# pidshield-mk-3_2.net
KiCad netlist of a schematic drawn in EAGLE
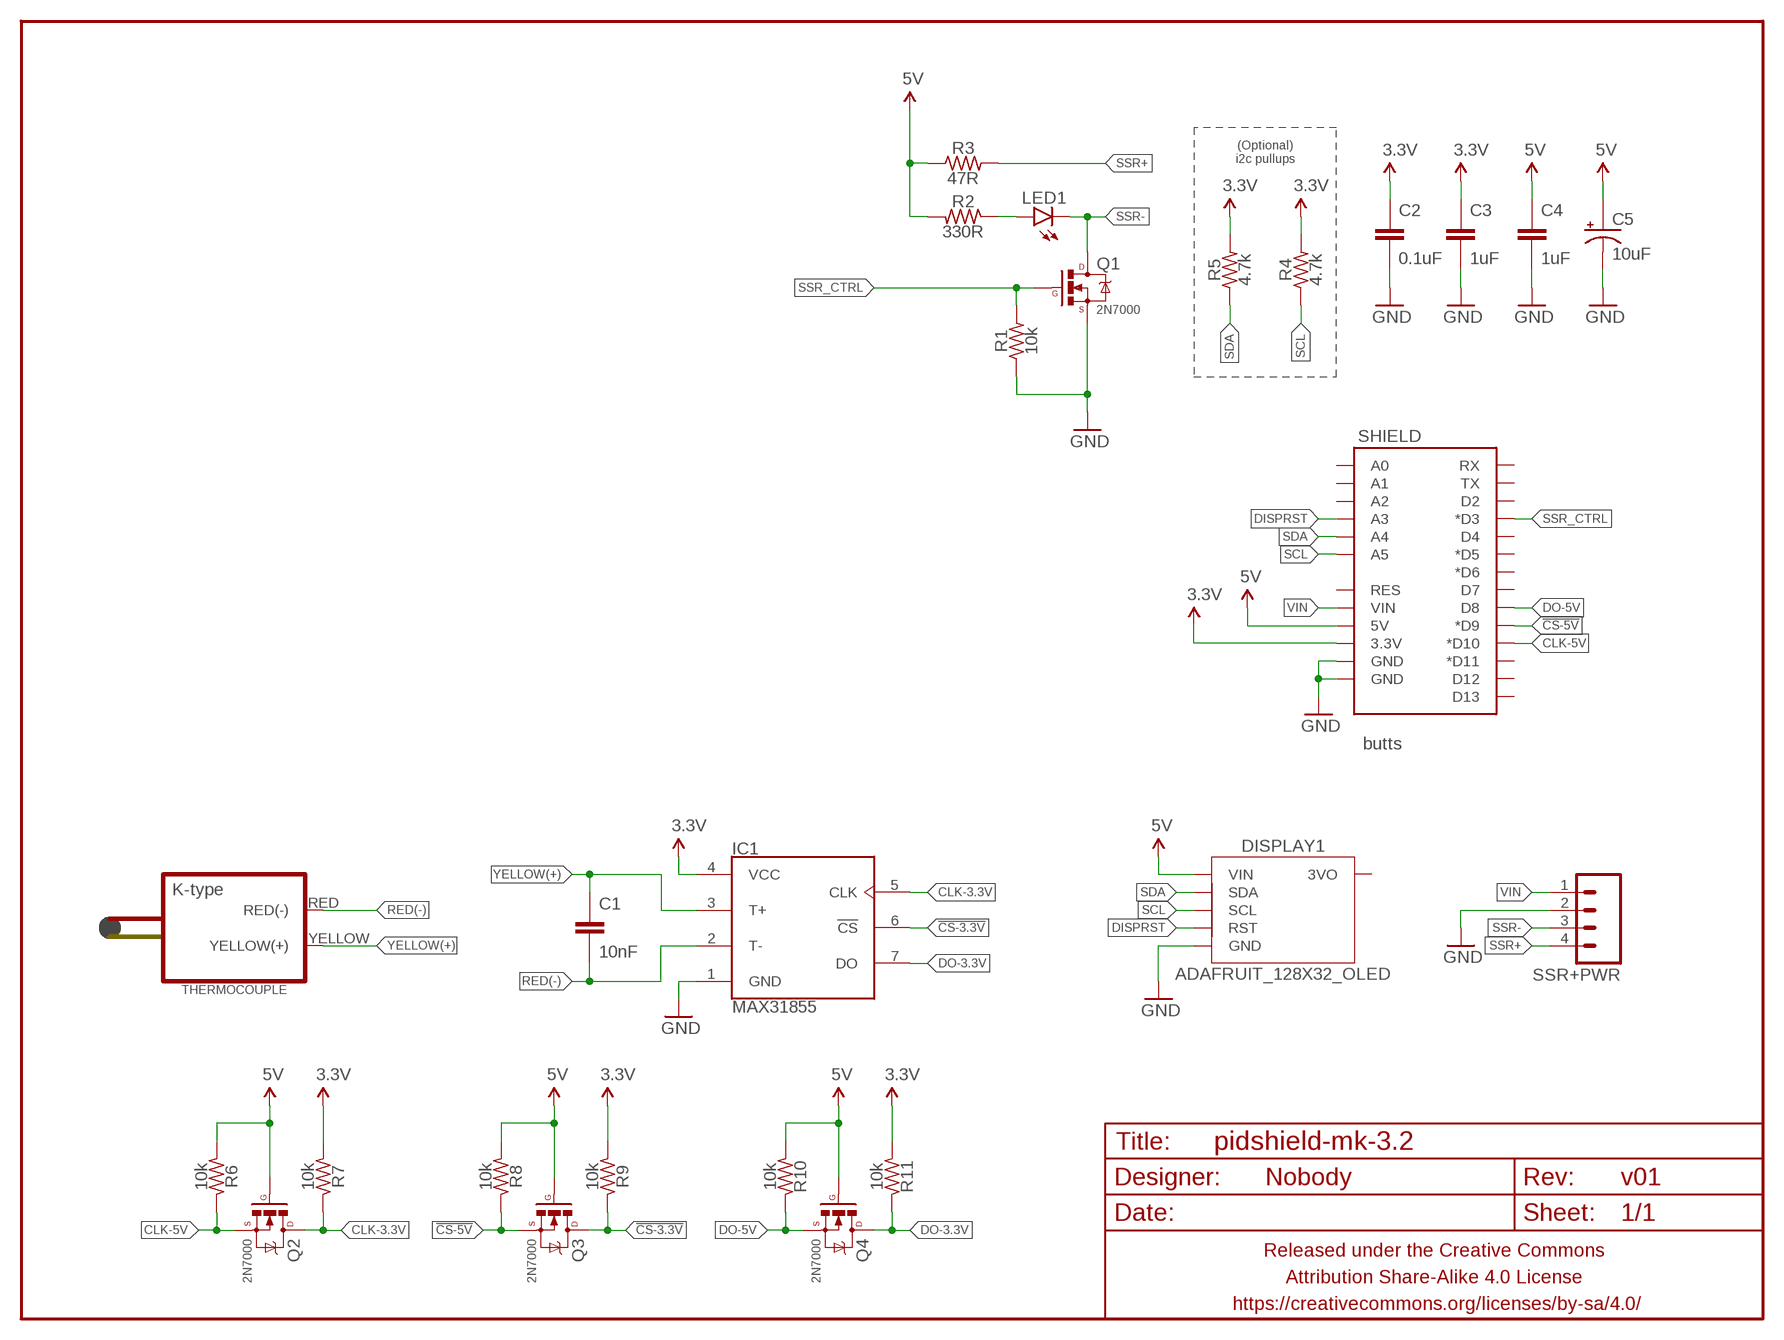
[diagram p0: schematic, sheet 1]

(export (version "E")
  (design (tool "Eeschema 10.0.6"))
  (components
    (comp (ref "C1")
      (value "10nF")
      (footprint "eagle-import:C0805")
      (libsource (lib "eagle-import") (part "CAPACITOR-CERAMICC0805"))
    )
    (comp (ref "C2")
      (value "0.1uF")
      (footprint "eagle-import:C025-024X044")
      (libsource (lib "eagle-import") (part "CAPACITOR-CERAMIC025-024X044"))
    )
    (comp (ref "C3")
      (value "1uF")
      (footprint "eagle-import:C025-024X044")
      (libsource (lib "eagle-import") (part "CAPACITOR-CERAMIC025-024X044"))
    )
    (comp (ref "C4")
      (value "1uF")
      (footprint "eagle-import:C025-024X044")
      (libsource (lib "eagle-import") (part "CAPACITOR-CERAMIC025-024X044"))
    )
    (comp (ref "C5")
      (value "10uF")
      (footprint "eagle-import:E2,5-6")
      (libsource (lib "eagle-import") (part "CAPACITOR-POLARIZEDE2.5-6"))
    )
    (comp (ref "DISPLAY1")
      (value "ADAFRUIT_128X32_OLED")
      (footprint "eagle-import:ADAFRUIT_128X32_OLED_I2C_CLOSER_NOTITLE")
      (libsource (lib "eagle-import") (part "ADAFRUIT_128X32_OLED_I2CNOTITLE"))
    )
    (comp (ref "FRAME1")
      (value "FRAME-LETTERNO_PACKAGE")
      (footprint "eagle-import:DUMMY")
      (fields (field (name "DESIGNER") "Nobody"))
      (libsource (lib "eagle-import") (part "FRAME-LETTERNO_PACKAGE"))
    )
    (comp (ref "IC1")
      (value "MAX31855")
      (footprint "eagle-import:SOIC127P600X175-8N")
      (libsource (lib "eagle-import") (part "MAX31855SOIC"))
    )
    (comp (ref "LED1")
      (value "LED3MM-LESS")
      (footprint "eagle-import:LED3MM-LESSSILK")
      (libsource (lib "eagle-import") (part "LED3MM-LESS"))
    )
    (comp (ref "Q1")
      (value "2N7000")
      (footprint "eagle-import:TO-92-AMMO")
      (libsource (lib "eagle-import") (part "MOSFET-NCHANNEL2N7000-AMMO"))
    )
    (comp (ref "Q2")
      (value "2N7000")
      (footprint "eagle-import:TO-92-AMMO")
      (libsource (lib "eagle-import") (part "MOSFET-NCHANNEL2N7000-AMMO"))
    )
    (comp (ref "Q3")
      (value "2N7000")
      (footprint "eagle-import:TO-92-AMMO")
      (libsource (lib "eagle-import") (part "MOSFET-NCHANNEL2N7000-AMMO"))
    )
    (comp (ref "Q4")
      (value "2N7000")
      (footprint "eagle-import:TO-92-AMMO")
      (libsource (lib "eagle-import") (part "MOSFET-NCHANNEL2N7000-AMMO"))
    )
    (comp (ref "R1")
      (value "10k")
      (footprint "eagle-import:RESISTOR-AXIAL-PTH-7.62MM")
      (libsource (lib "eagle-import") (part "RESISTORPTH-AXIAL-7.62MM"))
    )
    (comp (ref "R2")
      (value "330R")
      (footprint "eagle-import:RESISTOR-AXIAL-PTH-7.62MM")
      (libsource (lib "eagle-import") (part "RESISTORPTH-AXIAL-7.62MM"))
    )
    (comp (ref "R3")
      (value "47R")
      (footprint "eagle-import:RESISTOR-AXIAL-PTH-7.62MM")
      (libsource (lib "eagle-import") (part "RESISTORPTH-AXIAL-7.62MM"))
    )
    (comp (ref "R4")
      (value "4.7k")
      (footprint "eagle-import:RESISTOR-AXIAL-PTH-7.62MM")
      (libsource (lib "eagle-import") (part "RESISTORPTH-AXIAL-7.62MM"))
    )
    (comp (ref "R5")
      (value "4.7k")
      (footprint "eagle-import:RESISTOR-AXIAL-PTH-7.62MM")
      (libsource (lib "eagle-import") (part "RESISTORPTH-AXIAL-7.62MM"))
    )
    (comp (ref "R6")
      (value "10k")
      (footprint "eagle-import:RESISTOR-AXIAL-PTH-7.62MM")
      (libsource (lib "eagle-import") (part "RESISTORPTH-AXIAL-7.62MM"))
    )
    (comp (ref "R7")
      (value "10k")
      (footprint "eagle-import:RESISTOR-AXIAL-PTH-7.62MM")
      (libsource (lib "eagle-import") (part "RESISTORPTH-AXIAL-7.62MM"))
    )
    (comp (ref "R8")
      (value "10k")
      (footprint "eagle-import:RESISTOR-AXIAL-PTH-7.62MM")
      (libsource (lib "eagle-import") (part "RESISTORPTH-AXIAL-7.62MM"))
    )
    (comp (ref "R9")
      (value "10k")
      (footprint "eagle-import:RESISTOR-AXIAL-PTH-7.62MM")
      (libsource (lib "eagle-import") (part "RESISTORPTH-AXIAL-7.62MM"))
    )
    (comp (ref "R10")
      (value "10k")
      (footprint "eagle-import:RESISTOR-AXIAL-PTH-7.62MM")
      (libsource (lib "eagle-import") (part "RESISTORPTH-AXIAL-7.62MM"))
    )
    (comp (ref "R11")
      (value "10k")
      (footprint "eagle-import:RESISTOR-AXIAL-PTH-7.62MM")
      (libsource (lib "eagle-import") (part "RESISTORPTH-AXIAL-7.62MM"))
    )
    (comp (ref "SHIELD")
      (value "butts")
      (footprint "eagle-import:ARDUINO_SHIELD_SMALLER_NEKKID")
      (libsource (lib "eagle-import") (part "ARDUINO_SHIELD_SMALLERNEKKID"))
    )
    (comp (ref "SSR+PWR")
      (value "M04JST_XH_RA")
      (footprint "eagle-import:JST-4-XH-RA-PTH")
      (libsource (lib "eagle-import") (part "M04JST_XH_RA"))
    )
    (comp (ref "THERMOCOUPLE")
      (value "THERMOCOUPLE-CONNECTORMINI-PCB")
      (footprint "eagle-import:PCC-SMP")
      (libsource (lib "eagle-import") (part "THERMOCOUPLE-CONNECTORMINI-PCB"))
    )
  )
  (nets
    (net (code "1") (name "/~{CS-3.3V}") (class "Default")
      (node (ref "IC1") (pin "6") (pinfunction "~{CS}_6") (pintype "input"))
      (node (ref "Q3") (pin "3") (pinfunction "D_3") (pintype "passive"))
      (node (ref "R9") (pin "P$1") (pinfunction "1_P$1") (pintype "passive"))
    )
    (net (code "2") (name "/~{CS-5V}") (class "Default")
      (node (ref "Q3") (pin "1") (pinfunction "S_1") (pintype "passive"))
      (node (ref "R8") (pin "P$1") (pinfunction "1_P$1") (pintype "passive"))
      (node (ref "SHIELD") (pin "D9") (pinfunction "*D9_D9") (pintype "bidirectional"))
    )
    (net (code "3") (name "3.3V") (class "Default")
      (node (ref "C2") (pin "1") (pinfunction "1_1") (pintype "passive"))
      (node (ref "C3") (pin "1") (pinfunction "1_1") (pintype "passive"))
      (node (ref "IC1") (pin "4") (pinfunction "VCC_4") (pintype "power_in"))
      (node (ref "R11") (pin "P$2") (pinfunction "2_P$2") (pintype "passive"))
      (node (ref "R4") (pin "P$2") (pinfunction "2_P$2") (pintype "passive"))
      (node (ref "R5") (pin "P$2") (pinfunction "2_P$2") (pintype "passive"))
      (node (ref "R7") (pin "P$2") (pinfunction "2_P$2") (pintype "passive"))
      (node (ref "R9") (pin "P$2") (pinfunction "2_P$2") (pintype "passive"))
      (node (ref "SHIELD") (pin "3.3V") (pinfunction "3.3V_3.3V") (pintype "bidirectional"))
    )
    (net (code "4") (name "5V") (class "Default")
      (node (ref "C4") (pin "1") (pinfunction "1_1") (pintype "passive"))
      (node (ref "C5") (pin "+") (pinfunction "+_+") (pintype "passive"))
      (node (ref "DISPLAY1") (pin "VIN") (pinfunction "VIN_VIN") (pintype "bidirectional"))
      (node (ref "Q2") (pin "2") (pinfunction "G_2") (pintype "passive"))
      (node (ref "Q3") (pin "2") (pinfunction "G_2") (pintype "passive"))
      (node (ref "Q4") (pin "2") (pinfunction "G_2") (pintype "passive"))
      (node (ref "R10") (pin "P$2") (pinfunction "2_P$2") (pintype "passive"))
      (node (ref "R2") (pin "P$2") (pinfunction "2_P$2") (pintype "passive"))
      (node (ref "R3") (pin "P$1") (pinfunction "1_P$1") (pintype "passive"))
      (node (ref "R6") (pin "P$2") (pinfunction "2_P$2") (pintype "passive"))
      (node (ref "R8") (pin "P$2") (pinfunction "2_P$2") (pintype "passive"))
      (node (ref "SHIELD") (pin "5V") (pinfunction "5V_5V") (pintype "bidirectional"))
    )
    (net (code "5") (name "CLK-3.3V") (class "Default")
      (node (ref "IC1") (pin "5") (pinfunction "CLK_5") (pintype "input"))
      (node (ref "Q2") (pin "3") (pinfunction "D_3") (pintype "passive"))
      (node (ref "R7") (pin "P$1") (pinfunction "1_P$1") (pintype "passive"))
    )
    (net (code "6") (name "CLK-5V") (class "Default")
      (node (ref "Q2") (pin "1") (pinfunction "S_1") (pintype "passive"))
      (node (ref "R6") (pin "P$1") (pinfunction "1_P$1") (pintype "passive"))
      (node (ref "SHIELD") (pin "D10") (pinfunction "*D10_D10") (pintype "bidirectional"))
    )
    (net (code "7") (name "DISPRST") (class "Default")
      (node (ref "DISPLAY1") (pin "RST") (pinfunction "RST_RST") (pintype "bidirectional"))
      (node (ref "SHIELD") (pin "A3") (pinfunction "A3_A3") (pintype "bidirectional"))
    )
    (net (code "8") (name "DO-3.3V") (class "Default")
      (node (ref "IC1") (pin "7") (pinfunction "DO_7") (pintype "output"))
      (node (ref "Q4") (pin "3") (pinfunction "D_3") (pintype "passive"))
      (node (ref "R11") (pin "P$1") (pinfunction "1_P$1") (pintype "passive"))
    )
    (net (code "9") (name "DO-5V") (class "Default")
      (node (ref "Q4") (pin "1") (pinfunction "S_1") (pintype "passive"))
      (node (ref "R10") (pin "P$1") (pinfunction "1_P$1") (pintype "passive"))
      (node (ref "SHIELD") (pin "D8") (pinfunction "D8_D8") (pintype "bidirectional"))
    )
    (net (code "10") (name "GND") (class "Default")
      (node (ref "C2") (pin "2") (pinfunction "2_2") (pintype "passive"))
      (node (ref "C3") (pin "2") (pinfunction "2_2") (pintype "passive"))
      (node (ref "C4") (pin "2") (pinfunction "2_2") (pintype "passive"))
      (node (ref "C5") (pin "-") (pinfunction "-_-") (pintype "passive"))
      (node (ref "DISPLAY1") (pin "GND") (pinfunction "GND_GND") (pintype "bidirectional"))
      (node (ref "IC1") (pin "1") (pinfunction "GND_1") (pintype "power_in"))
      (node (ref "Q1") (pin "1") (pinfunction "S_1") (pintype "passive"))
      (node (ref "R1") (pin "P$1") (pinfunction "1_P$1") (pintype "passive"))
      (node (ref "SHIELD") (pin "GND@0") (pinfunction "GND_GND@0") (pintype "bidirectional"))
      (node (ref "SHIELD") (pin "GND@1") (pinfunction "GND_GND@1") (pintype "bidirectional"))
      (node (ref "SSR+PWR") (pin "2") (pinfunction "2_2") (pintype "passive"))
    )
    (net (code "11") (name "Net-(R2-1)") (class "Default")
      (node (ref "LED1") (pin "A") (pinfunction "A_A") (pintype "passive"))
      (node (ref "R2") (pin "P$1") (pinfunction "1_P$1") (pintype "passive"))
    )
    (net (code "12") (name "RED(-)") (class "Default")
      (node (ref "C1") (pin "2") (pinfunction "2_2") (pintype "passive"))
      (node (ref "IC1") (pin "2") (pinfunction "T-_2") (pintype "input"))
      (node (ref "THERMOCOUPLE") (pin "RED") (pinfunction "RED(-)_RED") (pintype "bidirectional"))
    )
    (net (code "13") (name "SCL") (class "Default")
      (node (ref "DISPLAY1") (pin "SCL") (pinfunction "SCL_SCL") (pintype "bidirectional"))
      (node (ref "R4") (pin "P$1") (pinfunction "1_P$1") (pintype "passive"))
      (node (ref "SHIELD") (pin "A5") (pinfunction "A5_A5") (pintype "bidirectional"))
    )
    (net (code "14") (name "SDA") (class "Default")
      (node (ref "DISPLAY1") (pin "SDA") (pinfunction "SDA_SDA") (pintype "bidirectional"))
      (node (ref "R5") (pin "P$1") (pinfunction "1_P$1") (pintype "passive"))
      (node (ref "SHIELD") (pin "A4") (pinfunction "A4_A4") (pintype "bidirectional"))
    )
    (net (code "15") (name "SSR+") (class "Default")
      (node (ref "R3") (pin "P$2") (pinfunction "2_P$2") (pintype "passive"))
      (node (ref "SSR+PWR") (pin "4") (pinfunction "4_4") (pintype "passive"))
    )
    (net (code "16") (name "SSR-") (class "Default")
      (node (ref "LED1") (pin "K") (pinfunction "C_K") (pintype "passive"))
      (node (ref "Q1") (pin "3") (pinfunction "D_3") (pintype "passive"))
      (node (ref "SSR+PWR") (pin "3") (pinfunction "3_3") (pintype "passive"))
    )
    (net (code "17") (name "SSR_CTRL") (class "Default")
      (node (ref "Q1") (pin "2") (pinfunction "G_2") (pintype "passive"))
      (node (ref "R1") (pin "P$2") (pinfunction "2_P$2") (pintype "passive"))
      (node (ref "SHIELD") (pin "D3") (pinfunction "*D3_D3") (pintype "bidirectional"))
    )
    (net (code "18") (name "VIN") (class "Default")
      (node (ref "SHIELD") (pin "VIN") (pinfunction "VIN_VIN") (pintype "bidirectional"))
      (node (ref "SSR+PWR") (pin "1") (pinfunction "1_1") (pintype "passive"))
    )
    (net (code "19") (name "YELLOW(+)") (class "Default")
      (node (ref "C1") (pin "1") (pinfunction "1_1") (pintype "passive"))
      (node (ref "IC1") (pin "3") (pinfunction "T+_3") (pintype "input"))
      (node (ref "THERMOCOUPLE") (pin "YELLOW") (pinfunction "YELLOW(+)_YELLOW") (pintype "bidirectional"))
    )
    (net (code "20") (name "unconnected-(DISPLAY1-Pad3VO)") (class "Default")
      (node (ref "DISPLAY1") (pin "3VO") (pinfunction "3VO_3VO") (pintype "bidirectional"))
    )
    (net (code "21") (name "unconnected-(SHIELD-*D5-PadD5)") (class "Default")
      (node (ref "SHIELD") (pin "D5") (pinfunction "*D5_D5") (pintype "bidirectional"))
    )
    (net (code "22") (name "unconnected-(SHIELD-*D6-PadD6)") (class "Default")
      (node (ref "SHIELD") (pin "D6") (pinfunction "*D6_D6") (pintype "bidirectional"))
    )
    (net (code "23") (name "unconnected-(SHIELD-*D11-PadD11)") (class "Default")
      (node (ref "SHIELD") (pin "D11") (pinfunction "*D11_D11") (pintype "bidirectional"))
    )
    (net (code "24") (name "unconnected-(SHIELD-PadA0)") (class "Default")
      (node (ref "SHIELD") (pin "A0") (pinfunction "A0_A0") (pintype "bidirectional"))
    )
    (net (code "25") (name "unconnected-(SHIELD-PadA1)") (class "Default")
      (node (ref "SHIELD") (pin "A1") (pinfunction "A1_A1") (pintype "bidirectional"))
    )
    (net (code "26") (name "unconnected-(SHIELD-PadA2)") (class "Default")
      (node (ref "SHIELD") (pin "A2") (pinfunction "A2_A2") (pintype "bidirectional"))
    )
    (net (code "27") (name "unconnected-(SHIELD-PadD2)") (class "Default")
      (node (ref "SHIELD") (pin "D2") (pinfunction "D2_D2") (pintype "bidirectional"))
    )
    (net (code "28") (name "unconnected-(SHIELD-PadD4)") (class "Default")
      (node (ref "SHIELD") (pin "D4") (pinfunction "D4_D4") (pintype "bidirectional"))
    )
    (net (code "29") (name "unconnected-(SHIELD-PadD7)") (class "Default")
      (node (ref "SHIELD") (pin "D7") (pinfunction "D7_D7") (pintype "bidirectional"))
    )
    (net (code "30") (name "unconnected-(SHIELD-PadD12)") (class "Default")
      (node (ref "SHIELD") (pin "D12") (pinfunction "D12_D12") (pintype "bidirectional"))
    )
    (net (code "31") (name "unconnected-(SHIELD-PadD13)") (class "Default")
      (node (ref "SHIELD") (pin "D13") (pinfunction "D13_D13") (pintype "bidirectional"))
    )
    (net (code "32") (name "unconnected-(SHIELD-PadRES)") (class "Default")
      (node (ref "SHIELD") (pin "RES") (pinfunction "RES_RES") (pintype "bidirectional"))
    )
    (net (code "33") (name "unconnected-(SHIELD-PadRX)") (class "Default")
      (node (ref "SHIELD") (pin "RX") (pinfunction "RX_RX") (pintype "bidirectional"))
    )
    (net (code "34") (name "unconnected-(SHIELD-PadTX)") (class "Default")
      (node (ref "SHIELD") (pin "TX") (pinfunction "TX_TX") (pintype "bidirectional"))
    )
  )
)
